# ETHERNET.net
KiCad netlist of a schematic drawn in Altium Designer
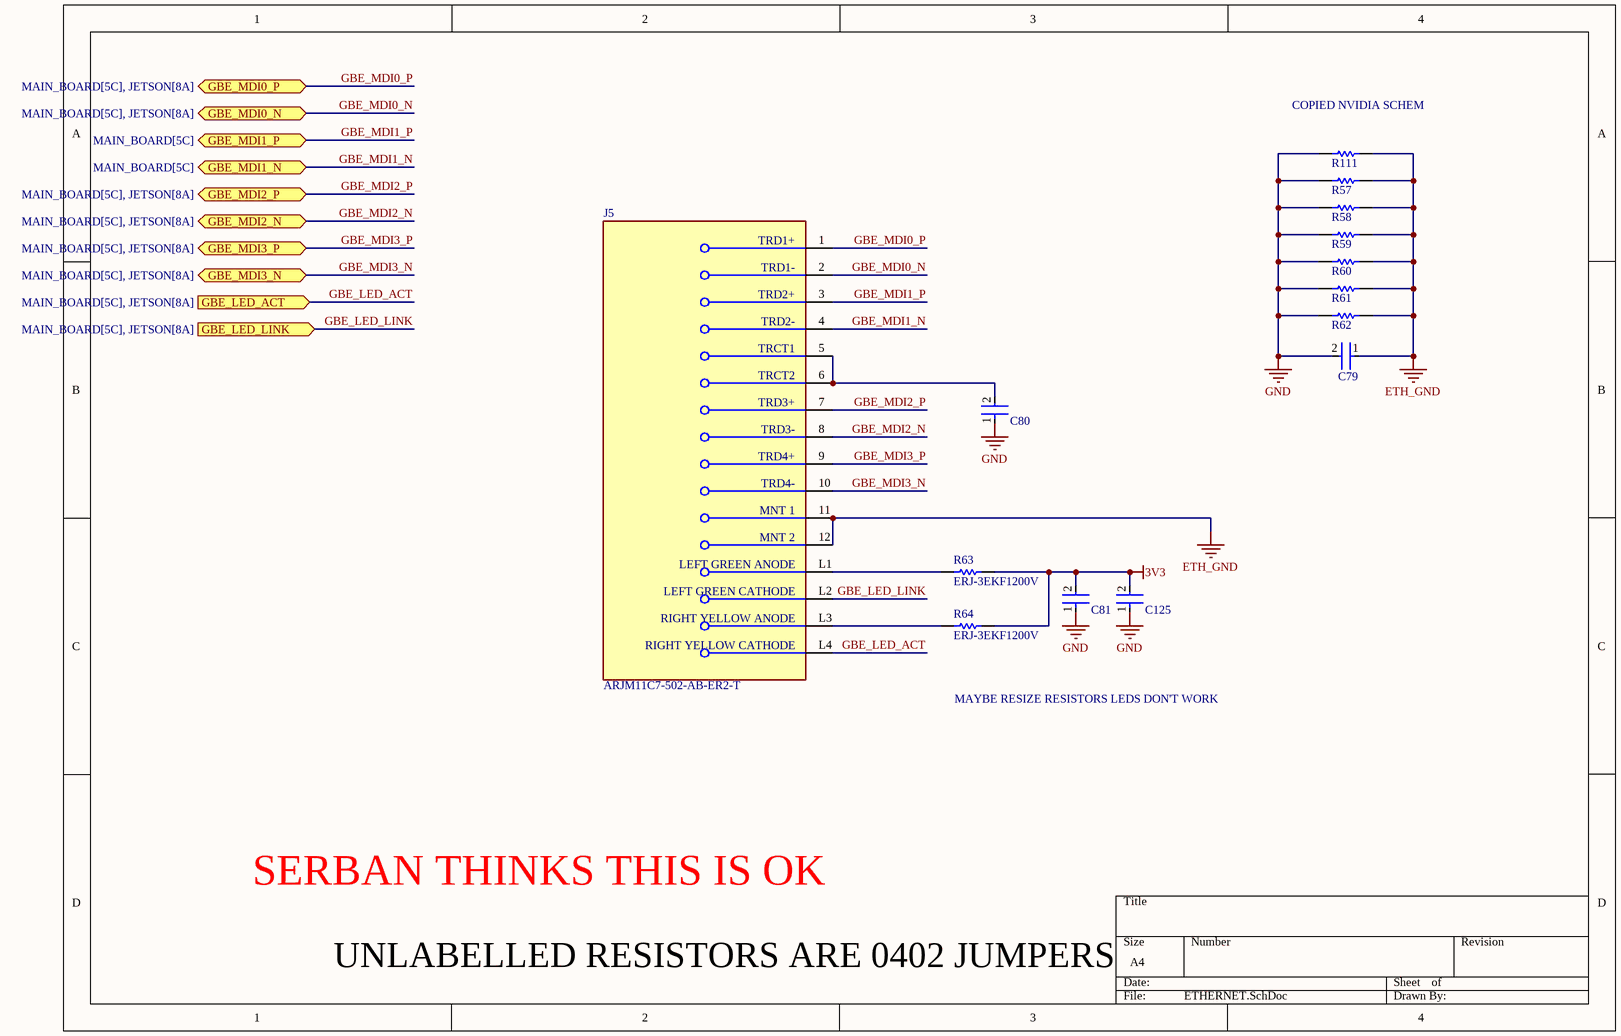
[diagram p0: ETHERNET.SchDoc]

(export (version "E")
  (design (tool "Eeschema 10.0.6"))
  (components
    (comp (ref "C79")
      (value "C1005X7R1H104K050BB")
      (footprint "FP-C1005-050-0_05-IPC_C")
      (description "Multilayer Ceramic Capacitors 100nF ±10% 50V X7R SMD 0402")
      (fields (field (name "VOLTAGE") "50V") (field (name "TOLERANCE") "10%"))
      (libsource (lib "Altium Content Vault") (part "b4654b650e69147ec39a6b967a45e02"))
    )
    (comp (ref "C80")
      (value "C1005X7R1H104K050BB")
      (footprint "FP-C1005-050-0_05-IPC_C")
      (description "Multilayer Ceramic Capacitors 100nF ±10% 50V X7R SMD 0402")
      (fields (field (name "VOLTAGE") "50V") (field (name "TOLERANCE") "10%"))
      (libsource (lib "Altium Content Vault") (part "b4654b650e69147ec39a6b967a45e02"))
    )
    (comp (ref "C81")
      (value "C1005X7R1H104K050BB")
      (footprint "FP-C1005-050-0_05-IPC_C")
      (description "Multilayer Ceramic Capacitors 100nF ±10% 50V X7R SMD 0402")
      (fields (field (name "VOLTAGE") "50V") (field (name "TOLERANCE") "10%"))
      (libsource (lib "Altium Content Vault") (part "b4654b650e69147ec39a6b967a45e02"))
    )
    (comp (ref "C125")
      (value "C1005X7R1H104K050BB")
      (footprint "FP-C1005-050-0_05-IPC_C")
      (description "Multilayer Ceramic Capacitors 100nF ±10% 50V X7R SMD 0402")
      (fields (field (name "VOLTAGE") "50V") (field (name "TOLERANCE") "10%"))
      (libsource (lib "Altium Content Vault") (part "b4654b650e69147ec39a6b967a45e02"))
    )
    (comp (ref "J5")
      (value "ARJM11C7-502-AB-ER2-T")
      (footprint "FP-ARJM11C7-502-AB-ER2-T-MFG")
      (description "RJ45 JACK W/MAG 1X1 1000BASE-T")
      (fields
        (field (name "MANUFACTURER") "Abracon")
        (field (name "OCTOPART") "https://octopart.com/arjm11c7-502-ab-er2-t-abracon-86945316")
      )
      (libsource (lib "Altium Content Vault") (part "c9e9675df30893a1b3e4105448caa83"))
    )
    (comp (ref "R57")
      (value "0402 JUMPER 0 OHM")
      (footprint "RESC1005X40X25NL05T05")
      (description "READ THE NAME")
      (libsource (lib "uORocketry Hardware") (part "RES"))
    )
    (comp (ref "R58")
      (value "0402 JUMPER 0 OHM")
      (footprint "RESC1005X40X25NL05T05")
      (description "READ THE NAME")
      (libsource (lib "uORocketry Hardware") (part "RES"))
    )
    (comp (ref "R59")
      (value "0402 JUMPER 0 OHM")
      (footprint "RESC1005X40X25NL05T05")
      (description "READ THE NAME")
      (libsource (lib "uORocketry Hardware") (part "RES"))
    )
    (comp (ref "R60")
      (value "0603 JUMPER")
      (footprint "RESC1609X55X30ML15T15")
      (description "READ THE NAME")
      (libsource (lib "uORocketry Hardware") (part "RES-2"))
    )
    (comp (ref "R61")
      (value "0603 JUMPER")
      (footprint "RESC1609X55X30ML15T15")
      (description "READ THE NAME")
      (libsource (lib "uORocketry Hardware") (part "RES-2"))
    )
    (comp (ref "R62")
      (value "0603 JUMPER")
      (footprint "RESC1609X55X30ML15T15")
      (description "READ THE NAME")
      (libsource (lib "uORocketry Hardware") (part "RES-2"))
    )
    (comp (ref "R63")
      (value "ERJ-3EKF1200V")
      (footprint "RESC1609X55X30ML15T15")
      (description "Chip Resistor, 120 Ohm, +/- 1%, 0.1 W, -55 to 155 degC, 0603 (1608 Metric), RoHS, Tape and Reel")
      (fields (field (name "TOLERANCE") "1%") (field (name "MANUFACTURER") "Panasonic"))
      (libsource (lib "Altium Content Vault") (part "RES-2"))
    )
    (comp (ref "R64")
      (value "ERJ-3EKF1200V")
      (footprint "RESC1609X55X30ML15T15")
      (description "Chip Resistor, 120 Ohm, +/- 1%, 0.1 W, -55 to 155 degC, 0603 (1608 Metric), RoHS, Tape and Reel")
      (fields (field (name "TOLERANCE") "1%") (field (name "MANUFACTURER") "Panasonic"))
      (libsource (lib "Altium Content Vault") (part "RES-2"))
    )
    (comp (ref "R111")
      (value "0402 JUMPER 0 OHM")
      (footprint "RESC1005X40X25NL05T05")
      (description "READ THE NAME")
      (libsource (lib "uORocketry Hardware") (part "RES"))
    )
  )
  (nets
    (net (code "1") (name "/GBE_LED_ACT") (class "Default")
      (node (ref "J5") (pin "L4") (pinfunction "RIGHT_YELLOW_CATHODE_L4") (pintype "passive"))
    )
    (net (code "2") (name "/GBE_LED_LINK") (class "Default")
      (node (ref "J5") (pin "L2") (pinfunction "LEFT_GREEN_CATHODE_L2") (pintype "passive"))
    )
    (net (code "3") (name "/GBE_MDI0_N") (class "Default")
      (node (ref "J5") (pin "2") (pinfunction "TRD1-_2") (pintype "passive"))
    )
    (net (code "4") (name "/GBE_MDI0_P") (class "Default")
      (node (ref "J5") (pin "1") (pinfunction "TRD1+_1") (pintype "passive"))
    )
    (net (code "5") (name "/GBE_MDI1_N") (class "Default")
      (node (ref "J5") (pin "4") (pinfunction "TRD2-_4") (pintype "passive"))
    )
    (net (code "6") (name "/GBE_MDI1_P") (class "Default")
      (node (ref "J5") (pin "3") (pinfunction "TRD2+_3") (pintype "passive"))
    )
    (net (code "7") (name "/GBE_MDI2_N") (class "Default")
      (node (ref "J5") (pin "8") (pinfunction "TRD3-_8") (pintype "passive"))
    )
    (net (code "8") (name "/GBE_MDI2_P") (class "Default")
      (node (ref "J5") (pin "7") (pinfunction "TRD3+_7") (pintype "passive"))
    )
    (net (code "9") (name "/GBE_MDI3_N") (class "Default")
      (node (ref "J5") (pin "10") (pinfunction "TRD4-_10") (pintype "passive"))
    )
    (net (code "10") (name "/GBE_MDI3_P") (class "Default")
      (node (ref "J5") (pin "9") (pinfunction "TRD4+_9") (pintype "passive"))
    )
    (net (code "11") (name "3V3") (class "Default")
      (node (ref "C125") (pin "2") (pinfunction "2_2") (pintype "passive"))
      (node (ref "C81") (pin "2") (pinfunction "2_2") (pintype "passive"))
      (node (ref "R63") (pin "2") (pinfunction "2_2") (pintype "passive"))
      (node (ref "R64") (pin "2") (pinfunction "2_2") (pintype "passive"))
    )
    (net (code "12") (name "ETH_GND") (class "Default")
      (node (ref "C79") (pin "1") (pinfunction "1_1") (pintype "passive"))
      (node (ref "J5") (pin "11") (pinfunction "MNT_1_11") (pintype "passive"))
      (node (ref "J5") (pin "12") (pinfunction "MNT_2_12") (pintype "passive"))
      (node (ref "R111") (pin "2") (pinfunction "2_2") (pintype "passive"))
      (node (ref "R57") (pin "2") (pinfunction "2_2") (pintype "passive"))
      (node (ref "R58") (pin "2") (pinfunction "2_2") (pintype "passive"))
      (node (ref "R59") (pin "2") (pinfunction "2_2") (pintype "passive"))
      (node (ref "R60") (pin "2") (pinfunction "2_2") (pintype "passive"))
      (node (ref "R61") (pin "2") (pinfunction "2_2") (pintype "passive"))
      (node (ref "R62") (pin "2") (pinfunction "2_2") (pintype "passive"))
    )
    (net (code "13") (name "GND") (class "Default")
      (node (ref "C125") (pin "1") (pinfunction "1_1") (pintype "passive"))
      (node (ref "C79") (pin "2") (pinfunction "2_2") (pintype "passive"))
      (node (ref "C80") (pin "1") (pinfunction "1_1") (pintype "passive"))
      (node (ref "C81") (pin "1") (pinfunction "1_1") (pintype "passive"))
      (node (ref "R111") (pin "1") (pinfunction "1_1") (pintype "passive"))
      (node (ref "R57") (pin "1") (pinfunction "1_1") (pintype "passive"))
      (node (ref "R58") (pin "1") (pinfunction "1_1") (pintype "passive"))
      (node (ref "R59") (pin "1") (pinfunction "1_1") (pintype "passive"))
      (node (ref "R60") (pin "1") (pinfunction "1_1") (pintype "passive"))
      (node (ref "R61") (pin "1") (pinfunction "1_1") (pintype "passive"))
      (node (ref "R62") (pin "1") (pinfunction "1_1") (pintype "passive"))
    )
    (net (code "14") (name "Net-(J5-LEFT_GREEN_ANODE)") (class "Default")
      (node (ref "J5") (pin "L1") (pinfunction "LEFT_GREEN_ANODE_L1") (pintype "passive"))
      (node (ref "R63") (pin "1") (pinfunction "1_1") (pintype "passive"))
    )
    (net (code "15") (name "Net-(J5-RIGHT_YELLOW_ANODE)") (class "Default")
      (node (ref "J5") (pin "L3") (pinfunction "RIGHT_YELLOW_ANODE_L3") (pintype "passive"))
      (node (ref "R64") (pin "1") (pinfunction "1_1") (pintype "passive"))
    )
    (net (code "16") (name "Net-(J5-TRCT1)") (class "Default")
      (node (ref "C80") (pin "2") (pinfunction "2_2") (pintype "passive"))
      (node (ref "J5") (pin "5") (pinfunction "TRCT1_5") (pintype "passive"))
      (node (ref "J5") (pin "6") (pinfunction "TRCT2_6") (pintype "passive"))
    )
  )
)
